# IMU_TB.net
KiCad netlist of a schematic drawn in EAGLE
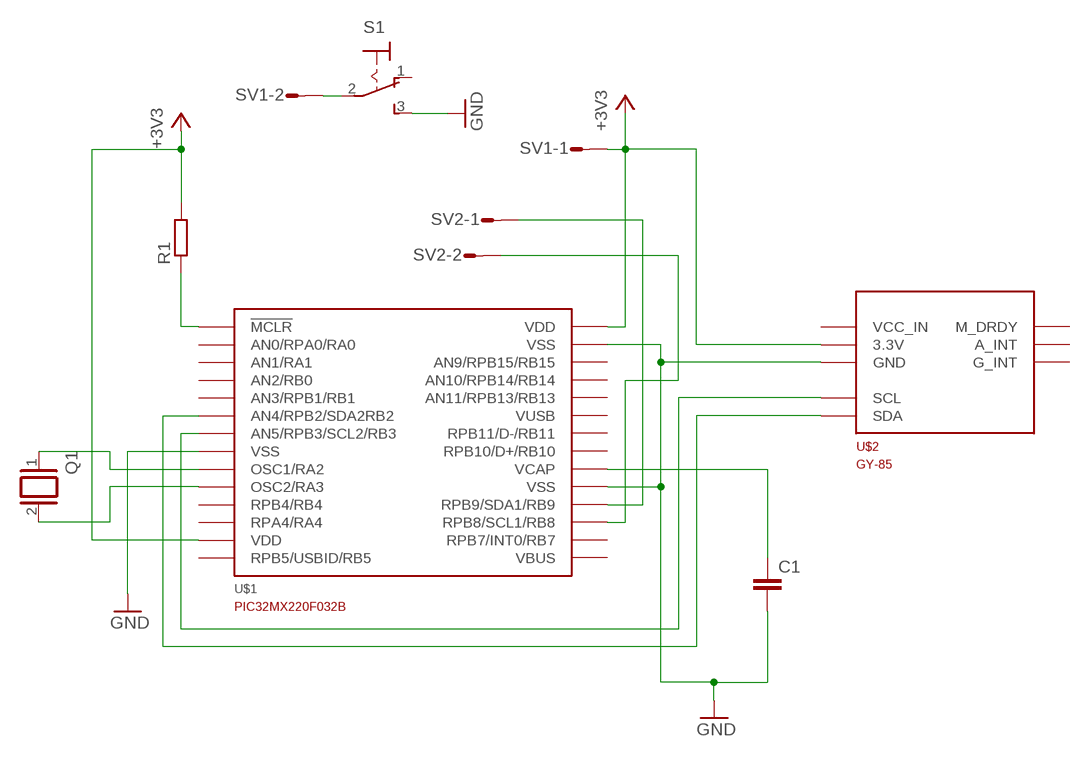
[diagram p0: schematic, sheet 1]

(export (version "E")
  (design (tool "Eeschema 10.0.6"))
  (components
    (comp (ref "C1")
      (value "C2,5-3")
      (footprint "eagle-import:C2.5-3")
      (libsource (lib "eagle-import") (part "C2,5-3"))
    )
    (comp (ref "Q1")
      (value "XTAL/S")
      (footprint "eagle-import:QS")
      (libsource (lib "eagle-import") (part "XTAL/S"))
    )
    (comp (ref "R1")
      (value "R-EU_0204/5")
      (footprint "eagle-import:0204_5")
      (libsource (lib "eagle-import") (part "R-EU_0204/5"))
    )
    (comp (ref "S1")
      (value "320-916")
      (footprint "eagle-import:320-916")
      (libsource (lib "eagle-import") (part "320-916"))
    )
    (comp (ref "SV1")
      (value "S02P")
      (footprint "eagle-import:S02P")
      (libsource (lib "eagle-import") (part "S02P"))
    )
    (comp (ref "SV2")
      (value "S02P")
      (footprint "eagle-import:S02P")
      (libsource (lib "eagle-import") (part "S02P"))
    )
    (comp (ref "U$1")
      (value "PIC32MX220F032B")
      (footprint "eagle-import:DIP28")
      (libsource (lib "eagle-import") (part "PIC32MX220F032B"))
    )
    (comp (ref "U$2")
      (value "GY-85")
      (footprint "eagle-import:GY-85")
      (libsource (lib "eagle-import") (part "GY-85"))
    )
  )
  (nets
    (net (code "1") (name "+3V3") (class "Default")
      (node (ref "R1") (pin "2") (pinfunction "2_2") (pintype "passive"))
      (node (ref "SV1") (pin "1") (pinfunction "S_1") (pintype "passive"))
      (node (ref "U$1") (pin "P$13") (pinfunction "VDD_P$13") (pintype "power_in"))
      (node (ref "U$1") (pin "P$28") (pinfunction "VDD_P$28") (pintype "power_in"))
      (node (ref "U$2") (pin "P$2") (pinfunction "3.3V_P$2") (pintype "power_in"))
    )
    (net (code "2") (name "/VCC_IN") (class "Default")
      (node (ref "U$2") (pin "P$1") (pinfunction "VCC_IN_P$1") (pintype "power_in"))
    )
    (net (code "3") (name "/VUSB") (class "Default")
      (node (ref "U$1") (pin "P$15") (pinfunction "VUSB_P$15") (pintype "power_in"))
    )
    (net (code "4") (name "GND") (class "Default")
      (node (ref "C1") (pin "2") (pinfunction "2_2") (pintype "passive"))
      (node (ref "S1") (pin "3") (pinfunction "S_3") (pintype "passive"))
      (node (ref "U$1") (pin "P$19") (pinfunction "VSS_P$19") (pintype "power_in"))
      (node (ref "U$1") (pin "P$27") (pinfunction "VSS_P$27") (pintype "power_in"))
      (node (ref "U$1") (pin "P$8") (pinfunction "VSS_P$8") (pintype "power_in"))
      (node (ref "U$2") (pin "P$3") (pinfunction "GND_P$3") (pintype "power_in"))
    )
    (net (code "5") (name "Net-(S1-P)") (class "Default")
      (node (ref "S1") (pin "2") (pinfunction "P_2") (pintype "passive"))
      (node (ref "SV1") (pin "2") (pinfunction "S_2") (pintype "passive"))
    )
    (net (code "6") (name "Net-(SV2A-S)") (class "Default")
      (node (ref "SV2") (pin "1") (pinfunction "S_1") (pintype "passive"))
      (node (ref "U$1") (pin "P$18") (pinfunction "RPB9/SDA1/RB9_P$18") (pintype "bidirectional"))
    )
    (net (code "7") (name "Net-(SV2B-S)") (class "Default")
      (node (ref "SV2") (pin "2") (pinfunction "S_2") (pintype "passive"))
      (node (ref "U$1") (pin "P$17") (pinfunction "RPB8/SCL1/RB8_P$17") (pintype "bidirectional"))
    )
    (net (code "8") (name "Net-(U$1-AN4{slash}RPB2{slash}SDA2RB2)") (class "Default")
      (node (ref "U$1") (pin "P$6") (pinfunction "AN4/RPB2/SDA2RB2_P$6") (pintype "bidirectional"))
      (node (ref "U$2") (pin "P$5") (pinfunction "SDA_P$5") (pintype "bidirectional"))
    )
    (net (code "9") (name "Net-(U$1-AN5{slash}RPB3{slash}SCL2{slash}RB3)") (class "Default")
      (node (ref "U$1") (pin "P$7") (pinfunction "AN5/RPB3/SCL2/RB3_P$7") (pintype "bidirectional"))
      (node (ref "U$2") (pin "P$4") (pinfunction "SCL_P$4") (pintype "bidirectional"))
    )
    (net (code "10") (name "Net-(U$1-OSC1{slash}RA2)") (class "Default")
      (node (ref "Q1") (pin "1") (pinfunction "1_1") (pintype "passive"))
      (node (ref "U$1") (pin "P$9") (pinfunction "OSC1/RA2_P$9") (pintype "bidirectional"))
    )
    (net (code "11") (name "Net-(U$1-OSC2{slash}RA3)") (class "Default")
      (node (ref "Q1") (pin "2") (pinfunction "2_2") (pintype "passive"))
      (node (ref "U$1") (pin "P$10") (pinfunction "OSC2/RA3_P$10") (pintype "bidirectional"))
    )
    (net (code "12") (name "Net-(U$1-VCAP)") (class "Default")
      (node (ref "C1") (pin "1") (pinfunction "1_1") (pintype "passive"))
      (node (ref "U$1") (pin "P$20") (pinfunction "VCAP_P$20") (pintype "bidirectional"))
    )
    (net (code "13") (name "Net-(U$1-~{MCLR})") (class "Default")
      (node (ref "R1") (pin "1") (pinfunction "1_1") (pintype "passive"))
      (node (ref "U$1") (pin "P$1") (pinfunction "~{MCLR}_P$1") (pintype "bidirectional"))
    )
    (net (code "14") (name "unconnected-(S1-O-Pad1)") (class "Default")
      (node (ref "S1") (pin "1") (pinfunction "O_1") (pintype "passive"))
    )
    (net (code "15") (name "unconnected-(U$1-AN0{slash}RPA0{slash}RA0-PadP$2)") (class "Default")
      (node (ref "U$1") (pin "P$2") (pinfunction "AN0/RPA0/RA0_P$2") (pintype "bidirectional"))
    )
    (net (code "16") (name "unconnected-(U$1-AN1{slash}RA1-PadP$3)") (class "Default")
      (node (ref "U$1") (pin "P$3") (pinfunction "AN1/RA1_P$3") (pintype "bidirectional"))
    )
    (net (code "17") (name "unconnected-(U$1-AN2{slash}RB0-PadP$4)") (class "Default")
      (node (ref "U$1") (pin "P$4") (pinfunction "AN2/RB0_P$4") (pintype "bidirectional"))
    )
    (net (code "18") (name "unconnected-(U$1-AN3{slash}RPB1{slash}RB1-PadP$5)") (class "Default")
      (node (ref "U$1") (pin "P$5") (pinfunction "AN3/RPB1/RB1_P$5") (pintype "bidirectional"))
    )
    (net (code "19") (name "unconnected-(U$1-AN9{slash}RPB15{slash}RB15-PadP$26)") (class "Default")
      (node (ref "U$1") (pin "P$26") (pinfunction "AN9/RPB15/RB15_P$26") (pintype "bidirectional"))
    )
    (net (code "20") (name "unconnected-(U$1-AN10{slash}RPB14{slash}RB14-PadP$25)") (class "Default")
      (node (ref "U$1") (pin "P$25") (pinfunction "AN10/RPB14/RB14_P$25") (pintype "bidirectional"))
    )
    (net (code "21") (name "unconnected-(U$1-AN11{slash}RPB13{slash}RB13-PadP$24)") (class "Default")
      (node (ref "U$1") (pin "P$24") (pinfunction "AN11/RPB13/RB13_P$24") (pintype "bidirectional"))
    )
    (net (code "22") (name "unconnected-(U$1-RPA4{slash}RA4-PadP$12)") (class "Default")
      (node (ref "U$1") (pin "P$12") (pinfunction "RPA4/RA4_P$12") (pintype "bidirectional"))
    )
    (net (code "23") (name "unconnected-(U$1-RPB4{slash}RB4-PadP$11)") (class "Default")
      (node (ref "U$1") (pin "P$11") (pinfunction "RPB4/RB4_P$11") (pintype "bidirectional"))
    )
    (net (code "24") (name "unconnected-(U$1-RPB5{slash}USBID{slash}RB5-PadP$14)") (class "Default")
      (node (ref "U$1") (pin "P$14") (pinfunction "RPB5/USBID/RB5_P$14") (pintype "bidirectional"))
    )
    (net (code "25") (name "unconnected-(U$1-RPB7{slash}INT0{slash}RB7-PadP$16)") (class "Default")
      (node (ref "U$1") (pin "P$16") (pinfunction "RPB7/INT0/RB7_P$16") (pintype "bidirectional"))
    )
    (net (code "26") (name "unconnected-(U$1-RPB10{slash}D+{slash}RB10-PadP$21)") (class "Default")
      (node (ref "U$1") (pin "P$21") (pinfunction "RPB10/D+/RB10_P$21") (pintype "bidirectional"))
    )
    (net (code "27") (name "unconnected-(U$1-RPB11{slash}D-{slash}RB11-PadP$22)") (class "Default")
      (node (ref "U$1") (pin "P$22") (pinfunction "RPB11/D-/RB11_P$22") (pintype "bidirectional"))
    )
    (net (code "28") (name "unconnected-(U$1-VBUS-PadP$23)") (class "Default")
      (node (ref "U$1") (pin "P$23") (pinfunction "VBUS_P$23") (pintype "bidirectional"))
    )
    (net (code "29") (name "unconnected-(U$2-A_INT-PadP$7)") (class "Default")
      (node (ref "U$2") (pin "P$7") (pinfunction "A_INT_P$7") (pintype "bidirectional"))
    )
    (net (code "30") (name "unconnected-(U$2-G_INT-PadP$8)") (class "Default")
      (node (ref "U$2") (pin "P$8") (pinfunction "G_INT_P$8") (pintype "bidirectional"))
    )
    (net (code "31") (name "unconnected-(U$2-M_DRDY-PadP$6)") (class "Default")
      (node (ref "U$2") (pin "P$6") (pinfunction "M_DRDY_P$6") (pintype "bidirectional"))
    )
  )
)
